# SCH_Dashboy_camera_NiMH_2023-03-14.net
KiCad netlist of a schematic drawn in EasyEDA
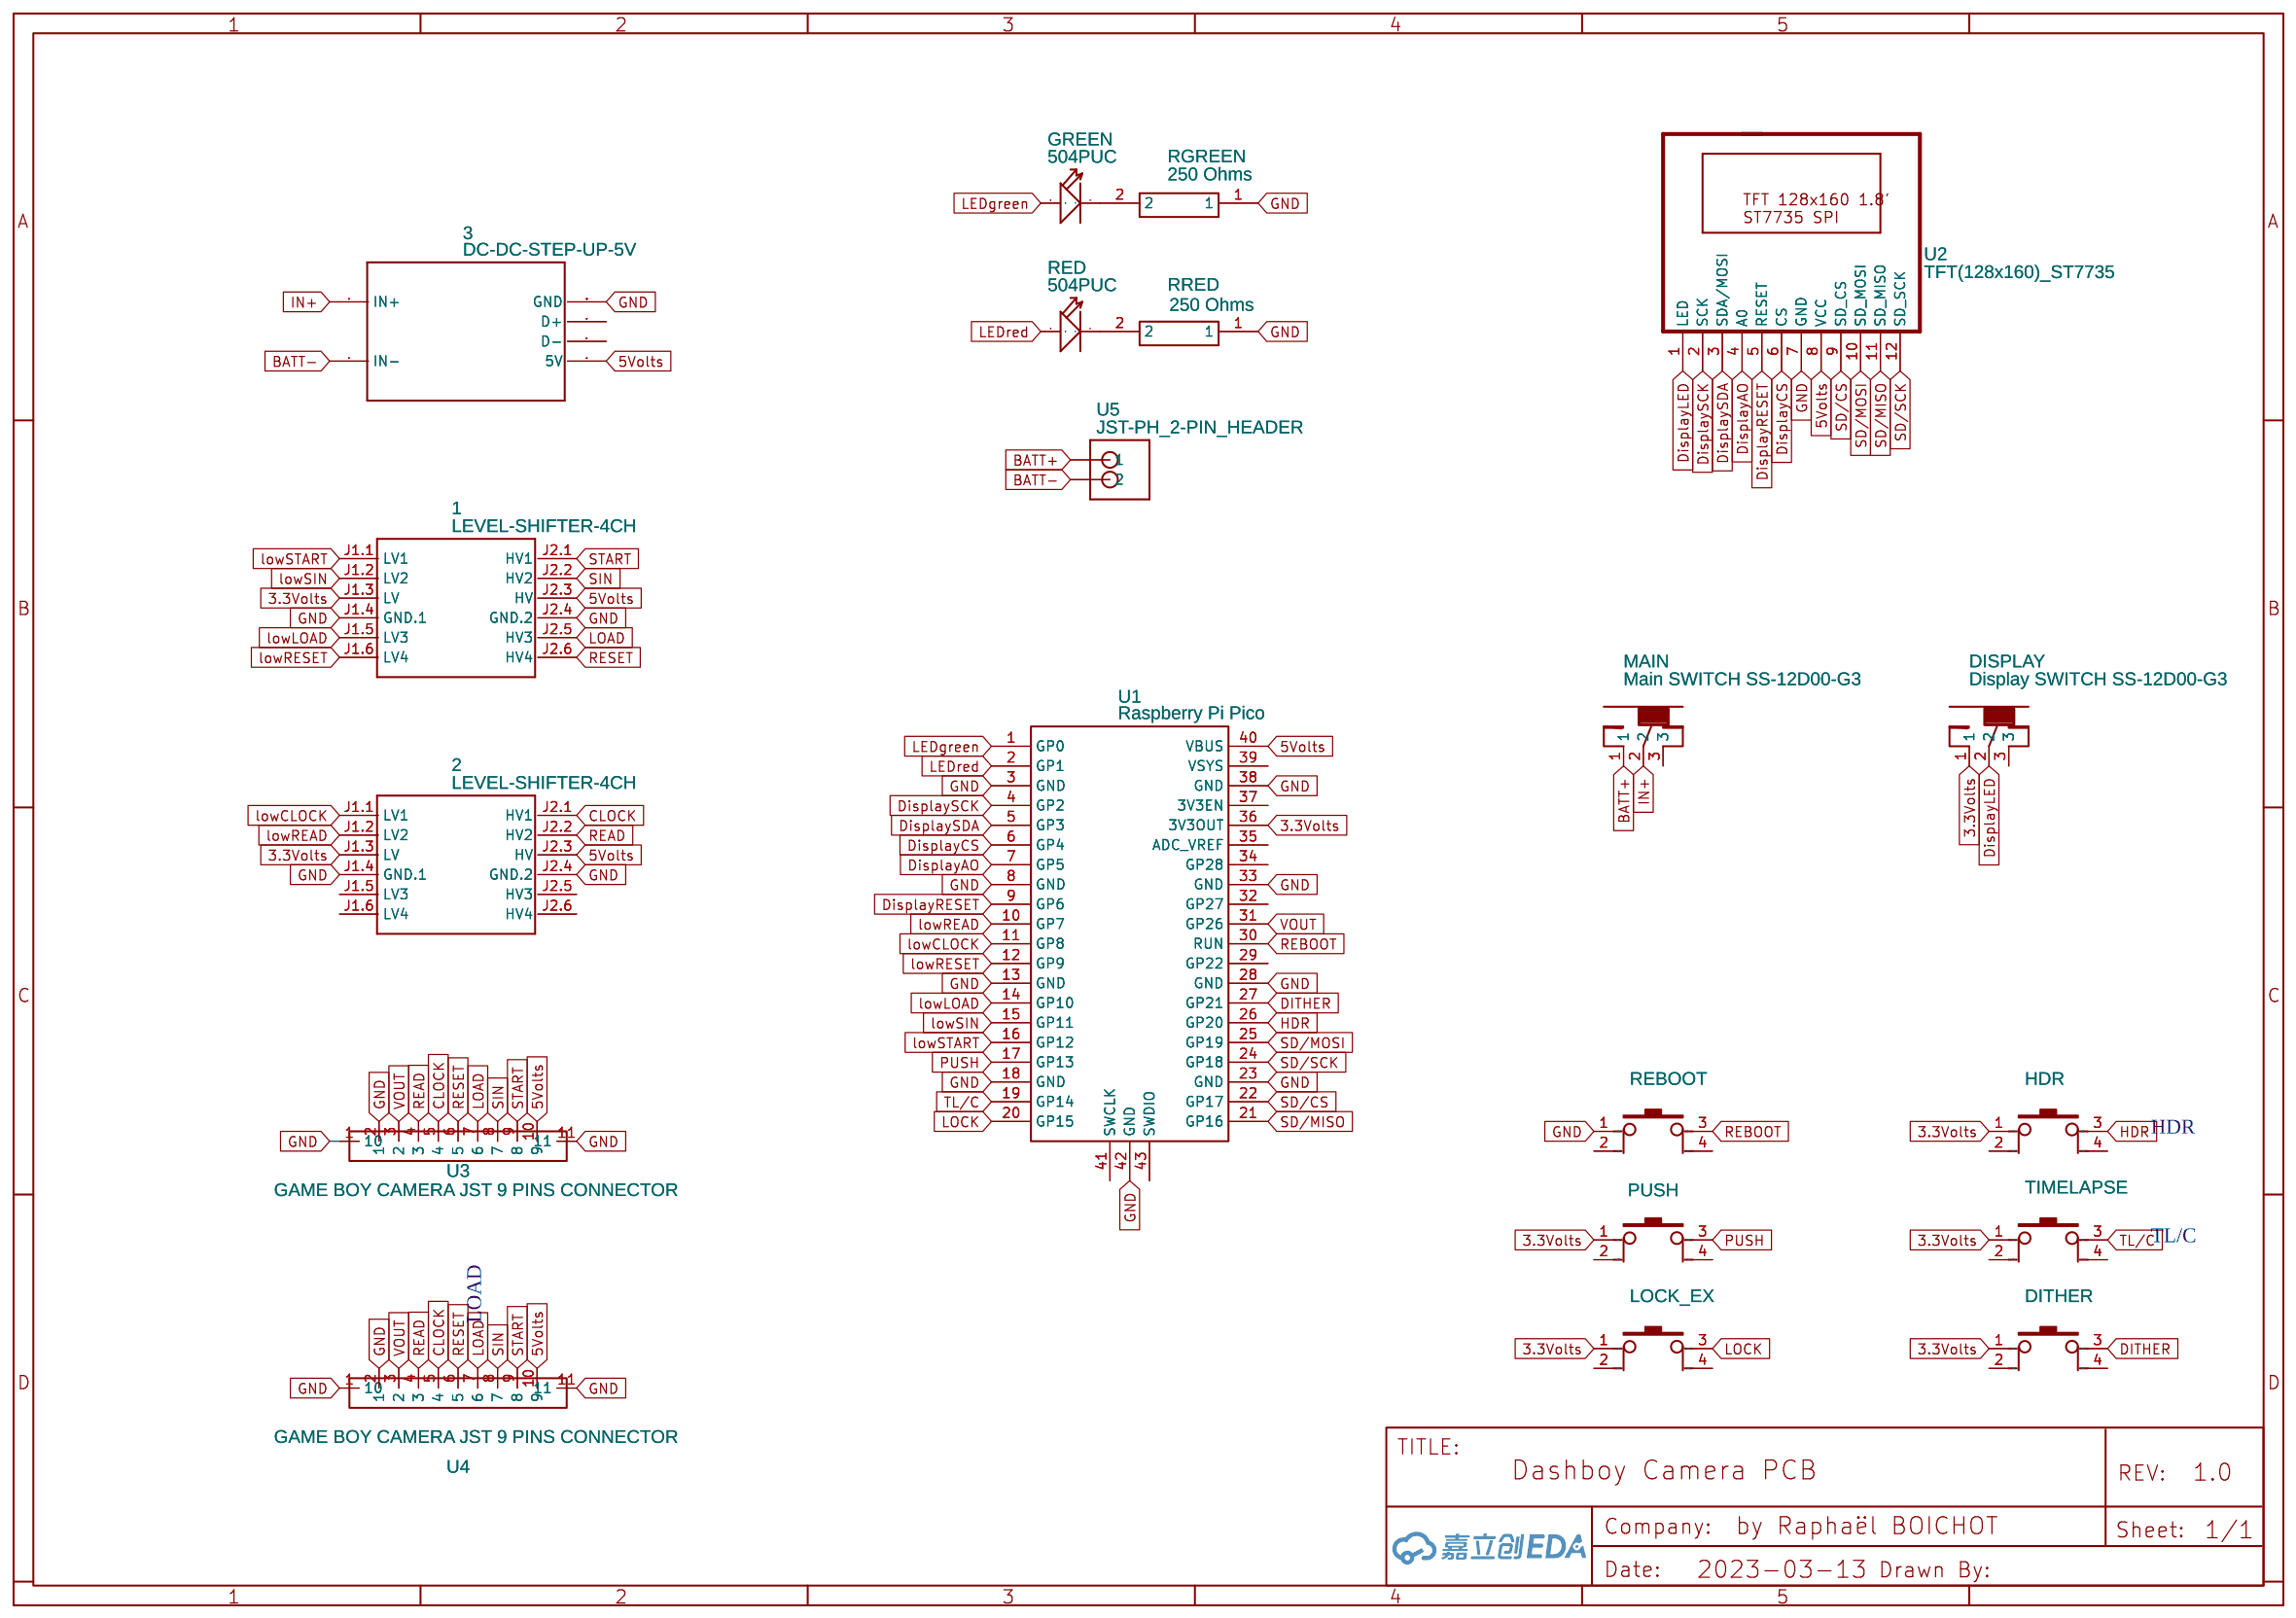
[diagram p0: schematic sheet]

(export (version "E")
  (design (tool "Eeschema 10.0.6"))
  (components
    (comp (ref "1") (value "LEVEL-SHIFTER-4CH") (libsource (lib "") (part "LEVEL-SHIFTER-4CH")))
    (comp (ref "2") (value "LEVEL-SHIFTER-4CH") (libsource (lib "") (part "LEVEL-SHIFTER-4CH")))
    (comp (ref "3") (value "DC-DC-STEP-UP-5V") (libsource (lib "") (part "DC-DC-STEP-UP-5V")))
    (comp (ref "DISPLAY")
      (value "Display SWITCH SS-12D00-G3")
      (fields (field (name "BOM_Manufacturer Part") "TOGGLE SWITCH SS-12D00-G3"))
      (libsource (lib "") (part "TOGGLE SWITCH SS-12D00-G3"))
    )
    (comp (ref "DITHER")
      (value "BoutonPoussoir")
      (fields
        (field (name "BOM_Manufacturer Part") "button6*6*8")
        (field (name "BOM_Supplier Part") "C59982")
      )
      (libsource (lib "") (part "BoutonPoussoir_2"))
    )
    (comp (ref "GREEN") (value "504PUC") (libsource (lib "") (part "504PUC")))
    (comp (ref "HDR")
      (value "BoutonPoussoir")
      (fields
        (field (name "BOM_Manufacturer Part") "button6*6*8")
        (field (name "BOM_Supplier Part") "C59982")
      )
      (libsource (lib "") (part "BoutonPoussoir_3"))
    )
    (comp (ref "LOCK_EX")
      (value "BoutonPoussoir")
      (fields
        (field (name "BOM_Manufacturer Part") "button6*6*8")
        (field (name "BOM_Supplier Part") "C59982")
      )
      (libsource (lib "") (part "BoutonPoussoir_5"))
    )
    (comp (ref "MAIN")
      (value "Main SWITCH SS-12D00-G3")
      (fields (field (name "BOM_Manufacturer Part") "TOGGLE SWITCH SS-12D00-G3"))
      (libsource (lib "") (part "TOGGLE SWITCH SS-12D00-G3_1"))
    )
    (comp (ref "PUSH")
      (value "BoutonPoussoir")
      (fields
        (field (name "BOM_Manufacturer Part") "button6*6*8")
        (field (name "BOM_Supplier Part") "C59982")
      )
      (libsource (lib "") (part "BoutonPoussoir_4"))
    )
    (comp (ref "REBOOT")
      (value "BoutonPoussoir")
      (fields
        (field (name "BOM_Manufacturer Part") "button6*6*8")
        (field (name "BOM_Supplier Part") "C59982")
      )
      (libsource (lib "") (part "BoutonPoussoir"))
    )
    (comp (ref "RED") (value "504PUC") (libsource (lib "") (part "504PUC_1")))
    (comp (ref "RGREEN") (value "250 Ohms") (libsource (lib "") (part "RESITOR")))
    (comp (ref "RRED") (value "250 Ohms") (libsource (lib "") (part "RESITOR_1")))
    (comp (ref "TIMELAPSE")
      (value "BoutonPoussoir")
      (fields
        (field (name "BOM_Manufacturer Part") "button6*6*8")
        (field (name "BOM_Supplier Part") "C59982")
      )
      (libsource (lib "") (part "BoutonPoussoir_1"))
    )
    (comp (ref "U1") (value "Raspberry Pi Pico") (libsource (lib "") (part "Raspberry Pi Pico")))
    (comp (ref "U2") (value "TFT(128x160)_ST7735") (libsource (lib "") (part "TFT(128x160)_ST7735")))
    (comp (ref "U3")
      (value "GAME BOY CAMERA JST 9 PINS CONNECTOR")
      (libsource (lib "") (part "GAME BOY CAMERA JST 9 PINS CONNECTOR"))
    )
    (comp (ref "U4")
      (value "GAME BOY CAMERA JST 9 PINS CONNECTOR")
      (libsource (lib "") (part "GAME BOY CAMERA JST 9 PINS CONNECTOR"))
    )
    (comp (ref "U5") (value "JST-PH_2-PIN_HEADER") (libsource (lib "") (part "JST-PH_2-PIN_HEADER")))
  )
  (nets
    (net (code "1") (name "3.3Volts") (class "Default")
      (node (ref "1") (pin "J1.3") (pinfunction "LV_J1.3") (pintype "bidirectional"))
      (node (ref "2") (pin "J1.3") (pinfunction "LV_J1.3") (pintype "bidirectional"))
      (node (ref "DISPLAY") (pin "1") (pinfunction "1_1") (pintype "bidirectional"))
      (node (ref "DITHER") (pin "1") (pinfunction "1_1") (pintype "input"))
      (node (ref "HDR") (pin "1") (pinfunction "1_1") (pintype "input"))
      (node (ref "LOCK_EX") (pin "1") (pinfunction "1_1") (pintype "input"))
      (node (ref "PUSH") (pin "1") (pinfunction "1_1") (pintype "input"))
      (node (ref "TIMELAPSE") (pin "1") (pinfunction "1_1") (pintype "input"))
      (node (ref "U1") (pin "36") (pinfunction "3V3OUT_36") (pintype "unspecified"))
    )
    (net (code "2") (name "5Volts") (class "Default")
      (node (ref "1") (pin "J2.3") (pinfunction "HV_J2.3") (pintype "bidirectional"))
      (node (ref "2") (pin "J2.3") (pinfunction "HV_J2.3") (pintype "bidirectional"))
      (node (ref "3") (pin "5V") (pinfunction "5V_5V") (pintype "bidirectional"))
      (node (ref "U1") (pin "40") (pinfunction "VBUS_40") (pintype "unspecified"))
      (node (ref "U2") (pin "8") (pinfunction "VCC_8") (pintype "input"))
      (node (ref "U3") (pin "10") (pinfunction "9_10") (pintype "unspecified"))
      (node (ref "U4") (pin "10") (pinfunction "9_10") (pintype "unspecified"))
    )
    (net (code "3") (name "BATT+") (class "Default")
      (node (ref "MAIN") (pin "1") (pinfunction "1_1") (pintype "bidirectional"))
      (node (ref "U5") (pin "P1") (pinfunction "1_P1") (pintype "unspecified"))
    )
    (net (code "4") (name "BATT-") (class "Default")
      (node (ref "3") (pin "IN-") (pinfunction "IN-_IN-") (pintype "bidirectional"))
      (node (ref "U5") (pin "P2") (pinfunction "2_P2") (pintype "unspecified"))
    )
    (net (code "5") (name "CLOCK") (class "Default")
      (node (ref "2") (pin "J2.1") (pinfunction "HV1_J2.1") (pintype "bidirectional"))
      (node (ref "U3") (pin "5") (pinfunction "4_5") (pintype "unspecified"))
      (node (ref "U4") (pin "5") (pinfunction "4_5") (pintype "unspecified"))
    )
    (net (code "6") (name "DITHER") (class "Default")
      (node (ref "DITHER") (pin "3") (pinfunction "3_3") (pintype "input"))
      (node (ref "U1") (pin "27") (pinfunction "GP21_27") (pintype "unspecified"))
    )
    (net (code "7") (name "DisplayAO") (class "Default")
      (node (ref "U1") (pin "7") (pinfunction "GP5_7") (pintype "unspecified"))
      (node (ref "U2") (pin "4") (pinfunction "A0_4") (pintype "input"))
    )
    (net (code "8") (name "DisplayCS") (class "Default")
      (node (ref "U1") (pin "6") (pinfunction "GP4_6") (pintype "unspecified"))
      (node (ref "U2") (pin "6") (pinfunction "CS_6") (pintype "input"))
    )
    (net (code "9") (name "DisplayLED") (class "Default")
      (node (ref "DISPLAY") (pin "2") (pinfunction "2_2") (pintype "bidirectional"))
      (node (ref "U2") (pin "1") (pinfunction "LED_1") (pintype "passive"))
    )
    (net (code "10") (name "DisplayRESET") (class "Default")
      (node (ref "U1") (pin "9") (pinfunction "GP6_9") (pintype "unspecified"))
      (node (ref "U2") (pin "5") (pinfunction "RESET_5") (pintype "input"))
    )
    (net (code "11") (name "DisplaySCK") (class "Default")
      (node (ref "U1") (pin "4") (pinfunction "GP2_4") (pintype "unspecified"))
      (node (ref "U2") (pin "2") (pinfunction "SCK_2") (pintype "output"))
    )
    (net (code "12") (name "DisplaySDA") (class "Default")
      (node (ref "U1") (pin "5") (pinfunction "GP3_5") (pintype "unspecified"))
      (node (ref "U2") (pin "3") (pinfunction "SDA/MOSI_3") (pintype "input"))
    )
    (net (code "13") (name "GND") (class "Default")
      (node (ref "1") (pin "J1.4") (pinfunction "GND.1_J1.4") (pintype "bidirectional"))
      (node (ref "1") (pin "J2.4") (pinfunction "GND.2_J2.4") (pintype "bidirectional"))
      (node (ref "2") (pin "J1.4") (pinfunction "GND.1_J1.4") (pintype "bidirectional"))
      (node (ref "2") (pin "J2.4") (pinfunction "GND.2_J2.4") (pintype "bidirectional"))
      (node (ref "3") (pin "GND") (pinfunction "GND_GND") (pintype "bidirectional"))
      (node (ref "REBOOT") (pin "1") (pinfunction "1_1") (pintype "input"))
      (node (ref "RGREEN") (pin "1") (pinfunction "1_1") (pintype "unspecified"))
      (node (ref "RRED") (pin "1") (pinfunction "1_1") (pintype "unspecified"))
      (node (ref "U1") (pin "13") (pinfunction "GND_13") (pintype "unspecified"))
      (node (ref "U1") (pin "18") (pinfunction "GND_18") (pintype "unspecified"))
      (node (ref "U1") (pin "23") (pinfunction "GND_23") (pintype "unspecified"))
      (node (ref "U1") (pin "28") (pinfunction "GND_28") (pintype "unspecified"))
      (node (ref "U1") (pin "3") (pinfunction "GND_3") (pintype "unspecified"))
      (node (ref "U1") (pin "33") (pinfunction "GND_33") (pintype "unspecified"))
      (node (ref "U1") (pin "38") (pinfunction "GND_38") (pintype "unspecified"))
      (node (ref "U1") (pin "42") (pinfunction "GND_42") (pintype "unspecified"))
      (node (ref "U1") (pin "8") (pinfunction "GND_8") (pintype "unspecified"))
      (node (ref "U2") (pin "7") (pinfunction "GND_7") (pintype "unspecified"))
      (node (ref "U3") (pin "1") (pinfunction "10_1") (pintype "unspecified"))
      (node (ref "U3") (pin "11") (pinfunction "11_11") (pintype "unspecified"))
      (node (ref "U3") (pin "2") (pinfunction "1_2") (pintype "unspecified"))
      (node (ref "U4") (pin "1") (pinfunction "10_1") (pintype "unspecified"))
      (node (ref "U4") (pin "11") (pinfunction "11_11") (pintype "unspecified"))
      (node (ref "U4") (pin "2") (pinfunction "1_2") (pintype "unspecified"))
    )
    (net (code "14") (name "HDR") (class "Default")
      (node (ref "HDR") (pin "3") (pinfunction "3_3") (pintype "input"))
      (node (ref "U1") (pin "26") (pinfunction "GP20_26") (pintype "unspecified"))
    )
    (net (code "15") (name "IN+") (class "Default")
      (node (ref "3") (pin "IN+") (pinfunction "IN+_IN+") (pintype "bidirectional"))
      (node (ref "MAIN") (pin "2") (pinfunction "2_2") (pintype "bidirectional"))
    )
    (net (code "16") (name "LEDgreen") (class "Default")
      (node (ref "GREEN") (pin "+") (pinfunction "+_+") (pintype "unspecified"))
      (node (ref "U1") (pin "1") (pinfunction "GP0_1") (pintype "unspecified"))
    )
    (net (code "17") (name "LEDred") (class "Default")
      (node (ref "RED") (pin "+") (pinfunction "+_+") (pintype "unspecified"))
      (node (ref "U1") (pin "2") (pinfunction "GP1_2") (pintype "unspecified"))
    )
    (net (code "18") (name "LOAD") (class "Default")
      (node (ref "1") (pin "J2.5") (pinfunction "HV3_J2.5") (pintype "bidirectional"))
      (node (ref "U3") (pin "7") (pinfunction "6_7") (pintype "unspecified"))
      (node (ref "U4") (pin "7") (pinfunction "6_7") (pintype "unspecified"))
    )
    (net (code "19") (name "LOCK") (class "Default")
      (node (ref "LOCK_EX") (pin "3") (pinfunction "3_3") (pintype "input"))
      (node (ref "U1") (pin "20") (pinfunction "GP15_20") (pintype "unspecified"))
    )
    (net (code "20") (name "Net-(GREEN-Pad-)") (class "Default")
      (node (ref "GREEN") (pin "-") (pinfunction "-_-") (pintype "unspecified"))
      (node (ref "RGREEN") (pin "2") (pinfunction "2_2") (pintype "unspecified"))
    )
    (net (code "21") (name "Net-(RED-Pad-)") (class "Default")
      (node (ref "RED") (pin "-") (pinfunction "-_-") (pintype "unspecified"))
      (node (ref "RRED") (pin "2") (pinfunction "2_2") (pintype "unspecified"))
    )
    (net (code "22") (name "PUSH") (class "Default")
      (node (ref "PUSH") (pin "3") (pinfunction "3_3") (pintype "input"))
      (node (ref "U1") (pin "17") (pinfunction "GP13_17") (pintype "unspecified"))
    )
    (net (code "23") (name "READ") (class "Default")
      (node (ref "2") (pin "J2.2") (pinfunction "HV2_J2.2") (pintype "bidirectional"))
      (node (ref "U3") (pin "4") (pinfunction "3_4") (pintype "unspecified"))
      (node (ref "U4") (pin "4") (pinfunction "3_4") (pintype "unspecified"))
    )
    (net (code "24") (name "REBOOT") (class "Default")
      (node (ref "REBOOT") (pin "3") (pinfunction "3_3") (pintype "input"))
      (node (ref "U1") (pin "30") (pinfunction "RUN_30") (pintype "unspecified"))
    )
    (net (code "25") (name "RESET") (class "Default")
      (node (ref "1") (pin "J2.6") (pinfunction "HV4_J2.6") (pintype "bidirectional"))
      (node (ref "U3") (pin "6") (pinfunction "5_6") (pintype "unspecified"))
      (node (ref "U4") (pin "6") (pinfunction "5_6") (pintype "unspecified"))
    )
    (net (code "26") (name "SD{slash}CS") (class "Default")
      (node (ref "U1") (pin "22") (pinfunction "GP17_22") (pintype "unspecified"))
      (node (ref "U2") (pin "9") (pinfunction "SD_CS_9") (pintype "input"))
    )
    (net (code "27") (name "SD{slash}MISO") (class "Default")
      (node (ref "U1") (pin "21") (pinfunction "GP16_21") (pintype "unspecified"))
      (node (ref "U2") (pin "11") (pinfunction "SD_MISO_11") (pintype "input"))
    )
    (net (code "28") (name "SD{slash}MOSI") (class "Default")
      (node (ref "U1") (pin "25") (pinfunction "GP19_25") (pintype "unspecified"))
      (node (ref "U2") (pin "10") (pinfunction "SD_MOSI_10") (pintype "input"))
    )
    (net (code "29") (name "SD{slash}SCK") (class "Default")
      (node (ref "U1") (pin "24") (pinfunction "GP18_24") (pintype "unspecified"))
      (node (ref "U2") (pin "12") (pinfunction "SD_SCK_12") (pintype "input"))
    )
    (net (code "30") (name "SIN") (class "Default")
      (node (ref "1") (pin "J2.2") (pinfunction "HV2_J2.2") (pintype "bidirectional"))
      (node (ref "U3") (pin "8") (pinfunction "7_8") (pintype "unspecified"))
      (node (ref "U4") (pin "8") (pinfunction "7_8") (pintype "unspecified"))
    )
    (net (code "31") (name "START") (class "Default")
      (node (ref "1") (pin "J2.1") (pinfunction "HV1_J2.1") (pintype "bidirectional"))
      (node (ref "U3") (pin "9") (pinfunction "8_9") (pintype "unspecified"))
      (node (ref "U4") (pin "9") (pinfunction "8_9") (pintype "unspecified"))
    )
    (net (code "32") (name "TL{slash}C") (class "Default")
      (node (ref "TIMELAPSE") (pin "3") (pinfunction "3_3") (pintype "input"))
      (node (ref "U1") (pin "19") (pinfunction "GP14_19") (pintype "unspecified"))
    )
    (net (code "33") (name "VOUT") (class "Default")
      (node (ref "U1") (pin "31") (pinfunction "GP26_31") (pintype "unspecified"))
      (node (ref "U3") (pin "3") (pinfunction "2_3") (pintype "unspecified"))
      (node (ref "U4") (pin "3") (pinfunction "2_3") (pintype "unspecified"))
    )
    (net (code "34") (name "lowCLOCK") (class "Default")
      (node (ref "2") (pin "J1.1") (pinfunction "LV1_J1.1") (pintype "bidirectional"))
      (node (ref "U1") (pin "11") (pinfunction "GP8_11") (pintype "unspecified"))
    )
    (net (code "35") (name "lowLOAD") (class "Default")
      (node (ref "1") (pin "J1.5") (pinfunction "LV3_J1.5") (pintype "bidirectional"))
      (node (ref "U1") (pin "14") (pinfunction "GP10_14") (pintype "unspecified"))
    )
    (net (code "36") (name "lowREAD") (class "Default")
      (node (ref "2") (pin "J1.2") (pinfunction "LV2_J1.2") (pintype "bidirectional"))
      (node (ref "U1") (pin "10") (pinfunction "GP7_10") (pintype "unspecified"))
    )
    (net (code "37") (name "lowRESET") (class "Default")
      (node (ref "1") (pin "J1.6") (pinfunction "LV4_J1.6") (pintype "bidirectional"))
      (node (ref "U1") (pin "12") (pinfunction "GP9_12") (pintype "unspecified"))
    )
    (net (code "38") (name "lowSIN") (class "Default")
      (node (ref "1") (pin "J1.2") (pinfunction "LV2_J1.2") (pintype "bidirectional"))
      (node (ref "U1") (pin "15") (pinfunction "GP11_15") (pintype "unspecified"))
    )
    (net (code "39") (name "lowSTART") (class "Default")
      (node (ref "1") (pin "J1.1") (pinfunction "LV1_J1.1") (pintype "bidirectional"))
      (node (ref "U1") (pin "16") (pinfunction "GP12_16") (pintype "unspecified"))
    )
    (net (code "40") (name "unconnected-(2-HV3-PadJ2.5)") (class "Default")
      (node (ref "2") (pin "J2.5") (pinfunction "HV3_J2.5") (pintype "bidirectional"))
    )
    (net (code "41") (name "unconnected-(2-HV4-PadJ2.6)") (class "Default")
      (node (ref "2") (pin "J2.6") (pinfunction "HV4_J2.6") (pintype "bidirectional"))
    )
    (net (code "42") (name "unconnected-(2-LV3-PadJ1.5)") (class "Default")
      (node (ref "2") (pin "J1.5") (pinfunction "LV3_J1.5") (pintype "bidirectional"))
    )
    (net (code "43") (name "unconnected-(2-LV4-PadJ1.6)") (class "Default")
      (node (ref "2") (pin "J1.6") (pinfunction "LV4_J1.6") (pintype "bidirectional"))
    )
    (net (code "44") (name "unconnected-(3-PadD+)") (class "Default")
      (node (ref "3") (pin "D+") (pinfunction "D+_D+") (pintype "bidirectional"))
    )
    (net (code "45") (name "unconnected-(3-PadD-)") (class "Default")
      (node (ref "3") (pin "D-") (pinfunction "D-_D-") (pintype "bidirectional"))
    )
    (net (code "46") (name "unconnected-(DISPLAY-Pad3)") (class "Default")
      (node (ref "DISPLAY") (pin "3") (pinfunction "3_3") (pintype "unspecified"))
    )
    (net (code "47") (name "unconnected-(DITHER-Pad2)") (class "Default")
      (node (ref "DITHER") (pin "2") (pinfunction "2_2") (pintype "input"))
    )
    (net (code "48") (name "unconnected-(DITHER-Pad4)") (class "Default")
      (node (ref "DITHER") (pin "4") (pinfunction "4_4") (pintype "input"))
    )
    (net (code "49") (name "unconnected-(HDR-Pad2)") (class "Default")
      (node (ref "HDR") (pin "2") (pinfunction "2_2") (pintype "input"))
    )
    (net (code "50") (name "unconnected-(HDR-Pad4)") (class "Default")
      (node (ref "HDR") (pin "4") (pinfunction "4_4") (pintype "input"))
    )
    (net (code "51") (name "unconnected-(LOCK_EX-Pad2)") (class "Default")
      (node (ref "LOCK_EX") (pin "2") (pinfunction "2_2") (pintype "input"))
    )
    (net (code "52") (name "unconnected-(LOCK_EX-Pad4)") (class "Default")
      (node (ref "LOCK_EX") (pin "4") (pinfunction "4_4") (pintype "input"))
    )
    (net (code "53") (name "unconnected-(MAIN-Pad3)") (class "Default")
      (node (ref "MAIN") (pin "3") (pinfunction "3_3") (pintype "unspecified"))
    )
    (net (code "54") (name "unconnected-(PUSH-Pad2)") (class "Default")
      (node (ref "PUSH") (pin "2") (pinfunction "2_2") (pintype "input"))
    )
    (net (code "55") (name "unconnected-(PUSH-Pad4)") (class "Default")
      (node (ref "PUSH") (pin "4") (pinfunction "4_4") (pintype "input"))
    )
    (net (code "56") (name "unconnected-(REBOOT-Pad2)") (class "Default")
      (node (ref "REBOOT") (pin "2") (pinfunction "2_2") (pintype "input"))
    )
    (net (code "57") (name "unconnected-(REBOOT-Pad4)") (class "Default")
      (node (ref "REBOOT") (pin "4") (pinfunction "4_4") (pintype "input"))
    )
    (net (code "58") (name "unconnected-(TIMELAPSE-Pad2)") (class "Default")
      (node (ref "TIMELAPSE") (pin "2") (pinfunction "2_2") (pintype "input"))
    )
    (net (code "59") (name "unconnected-(TIMELAPSE-Pad4)") (class "Default")
      (node (ref "TIMELAPSE") (pin "4") (pinfunction "4_4") (pintype "input"))
    )
    (net (code "60") (name "unconnected-(U1-3V3EN-Pad37)") (class "Default")
      (node (ref "U1") (pin "37") (pinfunction "3V3EN_37") (pintype "unspecified"))
    )
    (net (code "61") (name "unconnected-(U1-ADC_VREF-Pad35)") (class "Default")
      (node (ref "U1") (pin "35") (pinfunction "ADC_VREF_35") (pintype "unspecified"))
    )
    (net (code "62") (name "unconnected-(U1-GP22-Pad29)") (class "Default")
      (node (ref "U1") (pin "29") (pinfunction "GP22_29") (pintype "unspecified"))
    )
    (net (code "63") (name "unconnected-(U1-GP27-Pad32)") (class "Default")
      (node (ref "U1") (pin "32") (pinfunction "GP27_32") (pintype "unspecified"))
    )
    (net (code "64") (name "unconnected-(U1-GP28-Pad34)") (class "Default")
      (node (ref "U1") (pin "34") (pinfunction "GP28_34") (pintype "unspecified"))
    )
    (net (code "65") (name "unconnected-(U1-SWCLK-Pad41)") (class "Default")
      (node (ref "U1") (pin "41") (pinfunction "SWCLK_41") (pintype "unspecified"))
    )
    (net (code "66") (name "unconnected-(U1-SWDIO-Pad43)") (class "Default")
      (node (ref "U1") (pin "43") (pinfunction "SWDIO_43") (pintype "unspecified"))
    )
    (net (code "67") (name "unconnected-(U1-VSYS-Pad39)") (class "Default")
      (node (ref "U1") (pin "39") (pinfunction "VSYS_39") (pintype "unspecified"))
    )
  )
)
